# breadboard_rev08.net
KiCad netlist of a schematic drawn in EAGLE
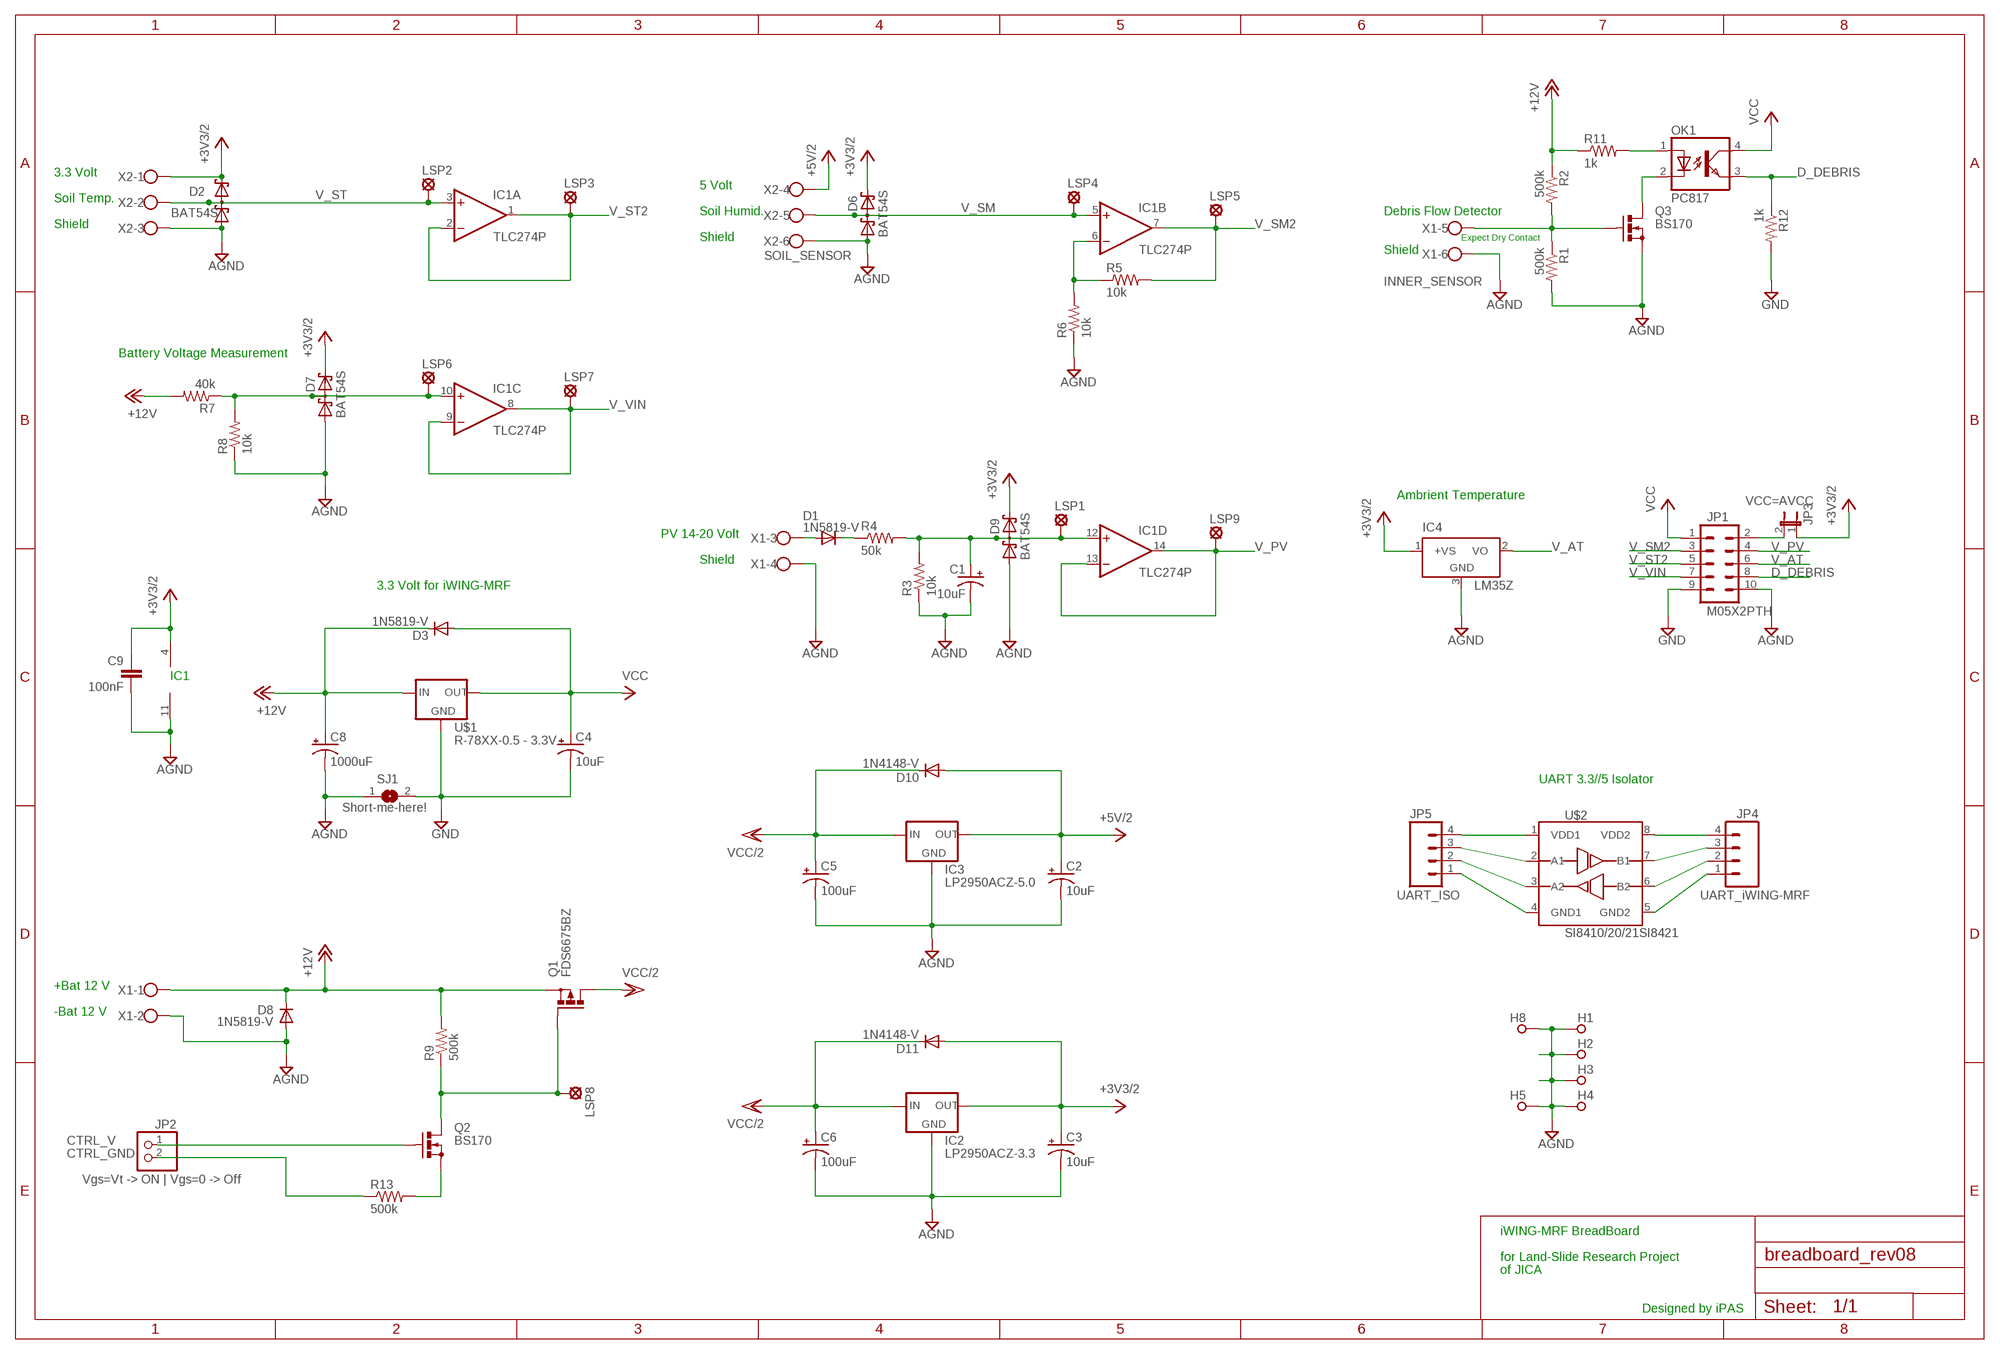
[diagram p0: schematic, sheet 1]

(export (version "E")
  (design (tool "Eeschema 10.0.6"))
  (components
    (comp (ref "C1")
      (value "10uF")
      (footprint "eagle-import:RCL_E2,5-7")
      (libsource (lib "eagle-import") (part "RCL_CPOL-USE2.5-7"))
    )
    (comp (ref "C2")
      (value "10uF")
      (footprint "eagle-import:RCL_E2,5-7")
      (libsource (lib "eagle-import") (part "RCL_CPOL-USE2.5-7"))
    )
    (comp (ref "C3")
      (value "10uF")
      (footprint "eagle-import:RCL_E2,5-7")
      (libsource (lib "eagle-import") (part "RCL_CPOL-USE2.5-7"))
    )
    (comp (ref "C4")
      (value "10uF")
      (footprint "eagle-import:RCL_E2,5-7")
      (libsource (lib "eagle-import") (part "RCL_CPOL-USE2.5-7"))
    )
    (comp (ref "C5")
      (value "100uF")
      (footprint "eagle-import:RCL_E2,5-7")
      (libsource (lib "eagle-import") (part "RCL_CPOL-USE2.5-7"))
    )
    (comp (ref "C6")
      (value "100uF")
      (footprint "eagle-import:RCL_E2,5-7")
      (libsource (lib "eagle-import") (part "RCL_CPOL-USE2.5-7"))
    )
    (comp (ref "C8")
      (value "1000uF")
      (footprint "eagle-import:RCL_E5-13")
      (libsource (lib "eagle-import") (part "RCL_CPOL-USE5-13"))
    )
    (comp (ref "C9")
      (value "100nF")
      (footprint "eagle-import:RCL_C050-025X075")
      (libsource (lib "eagle-import") (part "RCL_C-EU050-025X075"))
    )
    (comp (ref "D1")
      (value "1N5819-V")
      (footprint "eagle-import:DO41-150V")
      (libsource (lib "eagle-import") (part "1N5819-V"))
    )
    (comp (ref "D2")
      (value "BAT54S")
      (footprint "eagle-import:SOT23")
      (libsource (lib "eagle-import") (part "BAT54S"))
    )
    (comp (ref "D3")
      (value "1N5819-V")
      (footprint "eagle-import:DO41-150V")
      (libsource (lib "eagle-import") (part "1N5819-V"))
    )
    (comp (ref "D6")
      (value "BAT54S")
      (footprint "eagle-import:SOT23")
      (libsource (lib "eagle-import") (part "BAT54S"))
    )
    (comp (ref "D7")
      (value "BAT54S")
      (footprint "eagle-import:SOT23")
      (libsource (lib "eagle-import") (part "BAT54S"))
    )
    (comp (ref "D8")
      (value "1N5819-V")
      (footprint "eagle-import:DO41-150V")
      (libsource (lib "eagle-import") (part "1N5819-V"))
    )
    (comp (ref "D9")
      (value "BAT54S")
      (footprint "eagle-import:SOT23")
      (libsource (lib "eagle-import") (part "BAT54S"))
    )
    (comp (ref "D10")
      (value "1N4148-V")
      (footprint "eagle-import:DO35-100V")
      (libsource (lib "eagle-import") (part "1N4148-V"))
    )
    (comp (ref "D11")
      (value "1N4148-V")
      (footprint "eagle-import:DO35-100V")
      (libsource (lib "eagle-import") (part "1N4148-V"))
    )
    (comp (ref "H1")
      (value "SPECIAL_DRILL_0.1560")
      (footprint "eagle-import:PAD_0.1560")
      (libsource (lib "eagle-import") (part "SPECIAL_DRILL_0.1560"))
    )
    (comp (ref "H2")
      (value "SPECIAL_DRILL_0.1560")
      (footprint "eagle-import:PAD_0.1560")
      (libsource (lib "eagle-import") (part "SPECIAL_DRILL_0.1560"))
    )
    (comp (ref "H3")
      (value "SPECIAL_DRILL_0.1560")
      (footprint "eagle-import:PAD_0.1560")
      (libsource (lib "eagle-import") (part "SPECIAL_DRILL_0.1560"))
    )
    (comp (ref "H4")
      (value "SPECIAL_DRILL_0.1560")
      (footprint "eagle-import:PAD_0.1560")
      (libsource (lib "eagle-import") (part "SPECIAL_DRILL_0.1560"))
    )
    (comp (ref "H5")
      (value "SPECIAL_DRILL_0.1560")
      (footprint "eagle-import:PAD_0.1560")
      (libsource (lib "eagle-import") (part "SPECIAL_DRILL_0.1560"))
    )
    (comp (ref "H8")
      (value "SPECIAL_DRILL_0.1560")
      (footprint "eagle-import:PAD_0.1560")
      (libsource (lib "eagle-import") (part "SPECIAL_DRILL_0.1560"))
    )
    (comp (ref "IC1")
      (value "TLC274P")
      (footprint "eagle-import:DIL14")
      (libsource (lib "eagle-import") (part "TLC274P"))
    )
    (comp (ref "IC2")
      (value "LP2950ACZ-3.3")
      (footprint "eagle-import:TO92")
      (libsource (lib "eagle-import") (part "LP2950?ACZ-3.3"))
    )
    (comp (ref "IC3")
      (value "LP2950ACZ-5.0")
      (footprint "eagle-import:TO92")
      (libsource (lib "eagle-import") (part "LP2950?ACZ-5.0"))
    )
    (comp (ref "IC4")
      (value "LM35Z")
      (footprint "eagle-import:TO92")
      (libsource (lib "eagle-import") (part "LM35?Z"))
    )
    (comp (ref "JP1")
      (value "M05X2PTH")
      (footprint "eagle-import:AVR_ICSP")
      (libsource (lib "eagle-import") (part "M05X2PTH"))
    )
    (comp (ref "JP2")
      (value "Vgs=Vt -> ON | Vgs=0 -> Off")
      (footprint "eagle-import:1X02")
      (libsource (lib "eagle-import") (part "PINHD-1X2"))
    )
    (comp (ref "JP3")
      (value "VCC=AVCC")
      (footprint "eagle-import:JUMPER_JP1")
      (libsource (lib "eagle-import") (part "JP1E"))
    )
    (comp (ref "JP4")
      (value "UART_iWING-MRF")
      (footprint "eagle-import:MOLEX-1X4")
      (libsource (lib "eagle-import") (part "M04POLAR"))
    )
    (comp (ref "JP5")
      (value "UART_ISO")
      (footprint "eagle-import:MOLEX-1X4")
      (libsource (lib "eagle-import") (part "M04POLAR"))
    )
    (comp (ref "LSP1")
      (value "LSP13")
      (footprint "eagle-import:LSP13")
      (libsource (lib "eagle-import") (part "LSP13"))
    )
    (comp (ref "LSP2")
      (value "LSP13")
      (footprint "eagle-import:LSP13")
      (libsource (lib "eagle-import") (part "LSP13"))
    )
    (comp (ref "LSP3")
      (value "LSP13")
      (footprint "eagle-import:LSP13")
      (libsource (lib "eagle-import") (part "LSP13"))
    )
    (comp (ref "LSP4")
      (value "LSP13")
      (footprint "eagle-import:LSP13")
      (libsource (lib "eagle-import") (part "LSP13"))
    )
    (comp (ref "LSP5")
      (value "LSP13")
      (footprint "eagle-import:LSP13")
      (libsource (lib "eagle-import") (part "LSP13"))
    )
    (comp (ref "LSP6")
      (value "LSP13")
      (footprint "eagle-import:LSP13")
      (libsource (lib "eagle-import") (part "LSP13"))
    )
    (comp (ref "LSP7")
      (value "LSP13")
      (footprint "eagle-import:LSP13")
      (libsource (lib "eagle-import") (part "LSP13"))
    )
    (comp (ref "LSP8")
      (value "LSP13")
      (footprint "eagle-import:LSP13")
      (libsource (lib "eagle-import") (part "LSP13"))
    )
    (comp (ref "LSP9")
      (value "LSP13")
      (footprint "eagle-import:LSP13")
      (libsource (lib "eagle-import") (part "LSP13"))
    )
    (comp (ref "OK1")
      (value "PC817")
      (footprint "eagle-import:DIL04")
      (fields (field (name "MPN") "PC817X4J000F"))
      (libsource (lib "eagle-import") (part "PC817"))
    )
    (comp (ref "Q1")
      (value "FDS6675BZ")
      (footprint "eagle-import:SO-08")
      (libsource (lib "eagle-import") (part "P-MOSFET-SO8"))
    )
    (comp (ref "Q2")
      (value "BS170")
      (footprint "eagle-import:SOT54E")
      (libsource (lib "eagle-import") (part "BS170"))
    )
    (comp (ref "Q3")
      (value "BS170")
      (footprint "eagle-import:SOT54E")
      (libsource (lib "eagle-import") (part "BS170"))
    )
    (comp (ref "R1")
      (value "500k")
      (footprint "eagle-import:RCL_0204_7")
      (libsource (lib "eagle-import") (part "RCL_R-US_0204/7"))
    )
    (comp (ref "R2")
      (value "500k")
      (footprint "eagle-import:RCL_0204_7")
      (libsource (lib "eagle-import") (part "RCL_R-US_0204/7"))
    )
    (comp (ref "R3")
      (value "10k")
      (footprint "eagle-import:RCL_0204_7")
      (libsource (lib "eagle-import") (part "RCL_R-US_0204/7"))
    )
    (comp (ref "R4")
      (value "50k")
      (footprint "eagle-import:RCL_0204_7")
      (libsource (lib "eagle-import") (part "RCL_R-US_0204/7"))
    )
    (comp (ref "R5")
      (value "10k")
      (footprint "eagle-import:RCL_0204_7")
      (libsource (lib "eagle-import") (part "RCL_R-US_0204/7"))
    )
    (comp (ref "R6")
      (value "10k")
      (footprint "eagle-import:RCL_0204_7")
      (libsource (lib "eagle-import") (part "RCL_R-US_0204/7"))
    )
    (comp (ref "R7")
      (value "40k")
      (footprint "eagle-import:RCL_0204_7")
      (libsource (lib "eagle-import") (part "RCL_R-US_0204/7"))
    )
    (comp (ref "R8")
      (value "10k")
      (footprint "eagle-import:RCL_0204_7")
      (libsource (lib "eagle-import") (part "RCL_R-US_0204/7"))
    )
    (comp (ref "R9")
      (value "500k")
      (footprint "eagle-import:RCL_0204_7")
      (libsource (lib "eagle-import") (part "RCL_R-US_0204/7"))
    )
    (comp (ref "R11")
      (value "1k")
      (footprint "eagle-import:RCL_0204_7")
      (libsource (lib "eagle-import") (part "RCL_R-US_0204/7"))
    )
    (comp (ref "R12")
      (value "1k")
      (footprint "eagle-import:RCL_0204_7")
      (libsource (lib "eagle-import") (part "RCL_R-US_0204/7"))
    )
    (comp (ref "R13")
      (value "500k")
      (footprint "eagle-import:RCL_0204_7")
      (libsource (lib "eagle-import") (part "RCL_R-US_0204/7"))
    )
    (comp (ref "SJ1")
      (value "Short-me-here!")
      (footprint "eagle-import:SJ")
      (libsource (lib "eagle-import") (part "SJ"))
    )
    (comp (ref "U$1")
      (value "R-78XX-0.5 - 3.3V")
      (footprint "eagle-import:SIP3")
      (libsource (lib "eagle-import") (part "R-78XX-0.5"))
    )
    (comp (ref "U$2")
      (value "SI8410/20/21SI8421")
      (footprint "eagle-import:SO-08")
      (libsource (lib "eagle-import") (part "SI8410/20/21SI8421"))
    )
    (comp (ref "X1")
      (value "INNER_SENSOR")
      (footprint "eagle-import:5EHDRC-6P")
      (libsource (lib "eagle-import") (part "5EHDRC-6P"))
    )
    (comp (ref "X2")
      (value "SOIL_SENSOR")
      (footprint "eagle-import:5EHDRC-6P")
      (libsource (lib "eagle-import") (part "5EHDRC-6P"))
    )
  )
  (nets
    (net (code "1") (name "+3V3{slash}2") (class "Default")
      (node (ref "C3") (pin "+") (pinfunction "+_+") (pintype "passive"))
      (node (ref "C9") (pin "1") (pinfunction "1_1") (pintype "passive"))
      (node (ref "D11") (pin "A") (pinfunction "A_A") (pintype "passive"))
      (node (ref "D2") (pin "2") (pinfunction "C2_2") (pintype "passive"))
      (node (ref "D6") (pin "2") (pinfunction "C2_2") (pintype "passive"))
      (node (ref "D7") (pin "2") (pinfunction "C2_2") (pintype "passive"))
      (node (ref "D9") (pin "2") (pinfunction "C2_2") (pintype "passive"))
      (node (ref "IC1") (pin "4") (pinfunction "V+_4") (pintype "power_in"))
      (node (ref "IC2") (pin "1") (pinfunction "OUT_1") (pintype "passive"))
      (node (ref "IC4") (pin "1") (pinfunction "+VS_1") (pintype "input"))
      (node (ref "JP3") (pin "1") (pinfunction "1_1") (pintype "passive"))
      (node (ref "X2") (pin "1") (pinfunction "KL_1") (pintype "passive"))
    )
    (net (code "2") (name "+5V{slash}2") (class "Default")
      (node (ref "C2") (pin "+") (pinfunction "+_+") (pintype "passive"))
      (node (ref "D10") (pin "A") (pinfunction "A_A") (pintype "passive"))
      (node (ref "IC3") (pin "1") (pinfunction "OUT_1") (pintype "passive"))
      (node (ref "X2") (pin "4") (pinfunction "KL_4") (pintype "passive"))
    )
    (net (code "3") (name "+12V") (class "Default")
      (node (ref "C8") (pin "+") (pinfunction "+_+") (pintype "passive"))
      (node (ref "D3") (pin "C") (pinfunction "C_C") (pintype "passive"))
      (node (ref "D8") (pin "C") (pinfunction "C_C") (pintype "passive"))
      (node (ref "Q1") (pin "1") (pinfunction "S_1") (pintype "passive"))
      (node (ref "Q1") (pin "2") (pinfunction "S_2") (pintype "passive"))
      (node (ref "Q1") (pin "3") (pinfunction "S_3") (pintype "passive"))
      (node (ref "R11") (pin "1") (pinfunction "1_1") (pintype "passive"))
      (node (ref "R2") (pin "1") (pinfunction "1_1") (pintype "passive"))
      (node (ref "R7") (pin "2") (pinfunction "2_2") (pintype "passive"))
      (node (ref "R9") (pin "2") (pinfunction "2_2") (pintype "passive"))
      (node (ref "U$1") (pin "1") (pinfunction "IN_1") (pintype "input"))
      (node (ref "X1") (pin "1") (pinfunction "KL_1") (pintype "passive"))
    )
    (net (code "4") (name "/CTRL_GND") (class "Default")
      (node (ref "JP2") (pin "2") (pinfunction "2_2") (pintype "passive"))
      (node (ref "R13") (pin "1") (pinfunction "1_1") (pintype "passive"))
    )
    (net (code "5") (name "/CTRL_V") (class "Default")
      (node (ref "JP2") (pin "1") (pinfunction "1_1") (pintype "passive"))
      (node (ref "Q2") (pin "G") (pinfunction "G_G") (pintype "passive"))
    )
    (net (code "6") (name "/D_DEBRIS") (class "Default")
      (node (ref "JP1") (pin "8") (pinfunction "8_8") (pintype "passive"))
      (node (ref "OK1") (pin "3") (pinfunction "EMIT_3") (pintype "passive"))
      (node (ref "R12") (pin "1") (pinfunction "1_1") (pintype "passive"))
    )
    (net (code "7") (name "/V_AT") (class "Default")
      (node (ref "IC4") (pin "2") (pinfunction "VO_2") (pintype "output"))
      (node (ref "JP1") (pin "6") (pinfunction "6_6") (pintype "passive"))
    )
    (net (code "8") (name "/V_PV") (class "Default")
      (node (ref "IC1") (pin "13") (pinfunction "-IN_13") (pintype "input"))
      (node (ref "IC1") (pin "14") (pinfunction "OUT_14") (pintype "output"))
      (node (ref "JP1") (pin "4") (pinfunction "4_4") (pintype "passive"))
      (node (ref "LSP9") (pin "MP") (pinfunction "MP_MP") (pintype "passive"))
    )
    (net (code "9") (name "/V_SM") (class "Default")
      (node (ref "D6") (pin "3") (pinfunction "C1A2_3") (pintype "passive"))
      (node (ref "IC1") (pin "5") (pinfunction "+IN_5") (pintype "input"))
      (node (ref "LSP4") (pin "MP") (pinfunction "MP_MP") (pintype "passive"))
      (node (ref "X2") (pin "5") (pinfunction "KL_5") (pintype "passive"))
    )
    (net (code "10") (name "/V_SM2") (class "Default")
      (node (ref "IC1") (pin "7") (pinfunction "OUT_7") (pintype "output"))
      (node (ref "JP1") (pin "3") (pinfunction "3_3") (pintype "passive"))
      (node (ref "LSP5") (pin "MP") (pinfunction "MP_MP") (pintype "passive"))
      (node (ref "R5") (pin "2") (pinfunction "2_2") (pintype "passive"))
    )
    (net (code "11") (name "/V_ST") (class "Default")
      (node (ref "D2") (pin "3") (pinfunction "C1A2_3") (pintype "passive"))
      (node (ref "IC1") (pin "3") (pinfunction "+IN_3") (pintype "input"))
      (node (ref "LSP2") (pin "MP") (pinfunction "MP_MP") (pintype "passive"))
      (node (ref "X2") (pin "2") (pinfunction "KL_2") (pintype "passive"))
    )
    (net (code "12") (name "/V_ST2") (class "Default")
      (node (ref "IC1") (pin "1") (pinfunction "OUT_1") (pintype "output"))
      (node (ref "IC1") (pin "2") (pinfunction "-IN_2") (pintype "input"))
      (node (ref "JP1") (pin "5") (pinfunction "5_5") (pintype "passive"))
      (node (ref "LSP3") (pin "MP") (pinfunction "MP_MP") (pintype "passive"))
    )
    (net (code "13") (name "/V_VIN") (class "Default")
      (node (ref "IC1") (pin "8") (pinfunction "OUT_8") (pintype "output"))
      (node (ref "IC1") (pin "9") (pinfunction "-IN_9") (pintype "input"))
      (node (ref "JP1") (pin "7") (pinfunction "7_7") (pintype "passive"))
      (node (ref "LSP7") (pin "MP") (pinfunction "MP_MP") (pintype "passive"))
    )
    (net (code "14") (name "AGND") (class "Default")
      (node (ref "C1") (pin "-") (pinfunction "-_-") (pintype "passive"))
      (node (ref "C2") (pin "-") (pinfunction "-_-") (pintype "passive"))
      (node (ref "C3") (pin "-") (pinfunction "-_-") (pintype "passive"))
      (node (ref "C5") (pin "-") (pinfunction "-_-") (pintype "passive"))
      (node (ref "C6") (pin "-") (pinfunction "-_-") (pintype "passive"))
      (node (ref "C8") (pin "-") (pinfunction "-_-") (pintype "passive"))
      (node (ref "C9") (pin "2") (pinfunction "2_2") (pintype "passive"))
      (node (ref "D2") (pin "1") (pinfunction "A1_1") (pintype "passive"))
      (node (ref "D6") (pin "1") (pinfunction "A1_1") (pintype "passive"))
      (node (ref "D7") (pin "1") (pinfunction "A1_1") (pintype "passive"))
      (node (ref "D8") (pin "A") (pinfunction "A_A") (pintype "passive"))
      (node (ref "D9") (pin "1") (pinfunction "A1_1") (pintype "passive"))
      (node (ref "H1") (pin "1") (pinfunction "1_1") (pintype "passive"))
      (node (ref "H2") (pin "1") (pinfunction "1_1") (pintype "passive"))
      (node (ref "H3") (pin "1") (pinfunction "1_1") (pintype "passive"))
      (node (ref "H4") (pin "1") (pinfunction "1_1") (pintype "passive"))
      (node (ref "H5") (pin "1") (pinfunction "1_1") (pintype "passive"))
      (node (ref "H8") (pin "1") (pinfunction "1_1") (pintype "passive"))
      (node (ref "IC1") (pin "11") (pinfunction "V-_11") (pintype "power_in"))
      (node (ref "IC2") (pin "2") (pinfunction "GND_2") (pintype "input"))
      (node (ref "IC3") (pin "2") (pinfunction "GND_2") (pintype "input"))
      (node (ref "IC4") (pin "3") (pinfunction "GND_3") (pintype "power_in"))
      (node (ref "JP1") (pin "10") (pinfunction "10_10") (pintype "passive"))
      (node (ref "Q3") (pin "S") (pinfunction "S_S") (pintype "passive"))
      (node (ref "R1") (pin "2") (pinfunction "2_2") (pintype "passive"))
      (node (ref "R3") (pin "1") (pinfunction "1_1") (pintype "passive"))
      (node (ref "R6") (pin "1") (pinfunction "1_1") (pintype "passive"))
      (node (ref "R8") (pin "1") (pinfunction "1_1") (pintype "passive"))
      (node (ref "SJ1") (pin "1") (pinfunction "1_1") (pintype "passive"))
      (node (ref "X1") (pin "2") (pinfunction "KL_2") (pintype "passive"))
      (node (ref "X1") (pin "4") (pinfunction "KL_4") (pintype "passive"))
      (node (ref "X1") (pin "6") (pinfunction "KL_6") (pintype "passive"))
      (node (ref "X2") (pin "3") (pinfunction "KL_3") (pintype "passive"))
      (node (ref "X2") (pin "6") (pinfunction "KL_6") (pintype "passive"))
    )
    (net (code "15") (name "GND") (class "Default")
      (node (ref "C4") (pin "-") (pinfunction "-_-") (pintype "passive"))
      (node (ref "JP1") (pin "9") (pinfunction "9_9") (pintype "passive"))
      (node (ref "R12") (pin "2") (pinfunction "2_2") (pintype "passive"))
      (node (ref "SJ1") (pin "2") (pinfunction "2_2") (pintype "passive"))
      (node (ref "U$1") (pin "2") (pinfunction "GND_2") (pintype "input"))
    )
    (net (code "16") (name "Net-(D1-PadC)") (class "Default")
      (node (ref "D1") (pin "C") (pinfunction "C_C") (pintype "passive"))
      (node (ref "R4") (pin "1") (pinfunction "1_1") (pintype "passive"))
    )
    (net (code "17") (name "Net-(D7-C1A2)") (class "Default")
      (node (ref "D7") (pin "3") (pinfunction "C1A2_3") (pintype "passive"))
      (node (ref "IC1") (pin "10") (pinfunction "+IN_10") (pintype "input"))
      (node (ref "LSP6") (pin "MP") (pinfunction "MP_MP") (pintype "passive"))
      (node (ref "R7") (pin "1") (pinfunction "1_1") (pintype "passive"))
      (node (ref "R8") (pin "2") (pinfunction "2_2") (pintype "passive"))
    )
    (net (code "18") (name "Net-(D9-C1A2)") (class "Default")
      (node (ref "C1") (pin "+") (pinfunction "+_+") (pintype "passive"))
      (node (ref "D9") (pin "3") (pinfunction "C1A2_3") (pintype "passive"))
      (node (ref "IC1") (pin "12") (pinfunction "+IN_12") (pintype "input"))
      (node (ref "LSP1") (pin "MP") (pinfunction "MP_MP") (pintype "passive"))
      (node (ref "R3") (pin "2") (pinfunction "2_2") (pintype "passive"))
      (node (ref "R4") (pin "2") (pinfunction "2_2") (pintype "passive"))
    )
    (net (code "19") (name "Net-(IC1B--IN)") (class "Default")
      (node (ref "IC1") (pin "6") (pinfunction "-IN_6") (pintype "input"))
      (node (ref "R5") (pin "1") (pinfunction "1_1") (pintype "passive"))
      (node (ref "R6") (pin "2") (pinfunction "2_2") (pintype "passive"))
    )
    (net (code "20") (name "Net-(JP1-Pad2)") (class "Default")
      (node (ref "JP1") (pin "2") (pinfunction "2_2") (pintype "passive"))
      (node (ref "JP3") (pin "2") (pinfunction "2_2") (pintype "passive"))
    )
    (net (code "21") (name "Net-(OK1-A)") (class "Default")
      (node (ref "OK1") (pin "1") (pinfunction "A_1") (pintype "passive"))
      (node (ref "R11") (pin "2") (pinfunction "2_2") (pintype "passive"))
    )
    (net (code "22") (name "Net-(OK1-C)") (class "Default")
      (node (ref "OK1") (pin "2") (pinfunction "C_2") (pintype "passive"))
      (node (ref "Q3") (pin "D") (pinfunction "D_D") (pintype "passive"))
    )
    (net (code "23") (name "Net-(Q1-G)") (class "Default")
      (node (ref "LSP8") (pin "MP") (pinfunction "MP_MP") (pintype "passive"))
      (node (ref "Q1") (pin "4") (pinfunction "G_4") (pintype "passive"))
      (node (ref "Q2") (pin "D") (pinfunction "D_D") (pintype "passive"))
      (node (ref "R9") (pin "1") (pinfunction "1_1") (pintype "passive"))
    )
    (net (code "24") (name "Net-(Q2-PadS)") (class "Default")
      (node (ref "Q2") (pin "S") (pinfunction "S_S") (pintype "passive"))
      (node (ref "R13") (pin "2") (pinfunction "2_2") (pintype "passive"))
    )
    (net (code "25") (name "Net-(U$2-A1)") (class "Default")
      (node (ref "JP5") (pin "3") (pinfunction "3_3") (pintype "passive"))
      (node (ref "U$2") (pin "2") (pinfunction "A1_2") (pintype "input"))
    )
    (net (code "26") (name "Net-(U$2-A2)") (class "Default")
      (node (ref "JP5") (pin "2") (pinfunction "2_2") (pintype "passive"))
      (node (ref "U$2") (pin "3") (pinfunction "A2_3") (pintype "output"))
    )
    (net (code "27") (name "Net-(U$2-B1)") (class "Default")
      (node (ref "JP4") (pin "3") (pinfunction "3_3") (pintype "passive"))
      (node (ref "U$2") (pin "7") (pinfunction "B1_7") (pintype "output"))
    )
    (net (code "28") (name "Net-(U$2-B2)") (class "Default")
      (node (ref "JP4") (pin "2") (pinfunction "2_2") (pintype "passive"))
      (node (ref "U$2") (pin "6") (pinfunction "B2_6") (pintype "input"))
    )
    (net (code "29") (name "Net-(U$2-GND1)") (class "Default")
      (node (ref "JP5") (pin "1") (pinfunction "1_1") (pintype "passive"))
      (node (ref "U$2") (pin "4") (pinfunction "GND1_4") (pintype "power_in"))
    )
    (net (code "30") (name "Net-(U$2-GND2)") (class "Default")
      (node (ref "JP4") (pin "1") (pinfunction "1_1") (pintype "passive"))
      (node (ref "U$2") (pin "5") (pinfunction "GND2_5") (pintype "power_in"))
    )
    (net (code "31") (name "Net-(U$2-VDD1)") (class "Default")
      (node (ref "JP5") (pin "4") (pinfunction "4_4") (pintype "passive"))
      (node (ref "U$2") (pin "1") (pinfunction "VDD1_1") (pintype "power_in"))
    )
    (net (code "32") (name "Net-(U$2-VDD2)") (class "Default")
      (node (ref "JP4") (pin "4") (pinfunction "4_4") (pintype "passive"))
      (node (ref "U$2") (pin "8") (pinfunction "VDD2_8") (pintype "power_in"))
    )
    (net (code "33") (name "Net-(X1C-KL)") (class "Default")
      (node (ref "D1") (pin "A") (pinfunction "A_A") (pintype "passive"))
      (node (ref "X1") (pin "3") (pinfunction "KL_3") (pintype "passive"))
    )
    (net (code "34") (name "Net-(X1E-KL)") (class "Default")
      (node (ref "Q3") (pin "G") (pinfunction "G_G") (pintype "passive"))
      (node (ref "R1") (pin "1") (pinfunction "1_1") (pintype "passive"))
      (node (ref "R2") (pin "2") (pinfunction "2_2") (pintype "passive"))
      (node (ref "X1") (pin "5") (pinfunction "KL_5") (pintype "passive"))
    )
    (net (code "35") (name "VCC") (class "Default")
      (node (ref "C4") (pin "+") (pinfunction "+_+") (pintype "passive"))
      (node (ref "D3") (pin "A") (pinfunction "A_A") (pintype "passive"))
      (node (ref "JP1") (pin "1") (pinfunction "1_1") (pintype "passive"))
      (node (ref "OK1") (pin "4") (pinfunction "COL_4") (pintype "passive"))
      (node (ref "U$1") (pin "3") (pinfunction "OUT_3") (pintype "passive"))
    )
    (net (code "36") (name "VCC{slash}2") (class "Default")
      (node (ref "C5") (pin "+") (pinfunction "+_+") (pintype "passive"))
      (node (ref "C6") (pin "+") (pinfunction "+_+") (pintype "passive"))
      (node (ref "D10") (pin "C") (pinfunction "C_C") (pintype "passive"))
      (node (ref "D11") (pin "C") (pinfunction "C_C") (pintype "passive"))
      (node (ref "IC2") (pin "3") (pinfunction "IN_3") (pintype "input"))
      (node (ref "IC3") (pin "3") (pinfunction "IN_3") (pintype "input"))
      (node (ref "Q1") (pin "5") (pinfunction "D_5") (pintype "passive"))
      (node (ref "Q1") (pin "6") (pinfunction "D_6") (pintype "passive"))
      (node (ref "Q1") (pin "7") (pinfunction "D_7") (pintype "passive"))
      (node (ref "Q1") (pin "8") (pinfunction "D_8") (pintype "passive"))
    )
  )
)
